# source_eagle.net
KiCad netlist of a schematic drawn in EAGLE
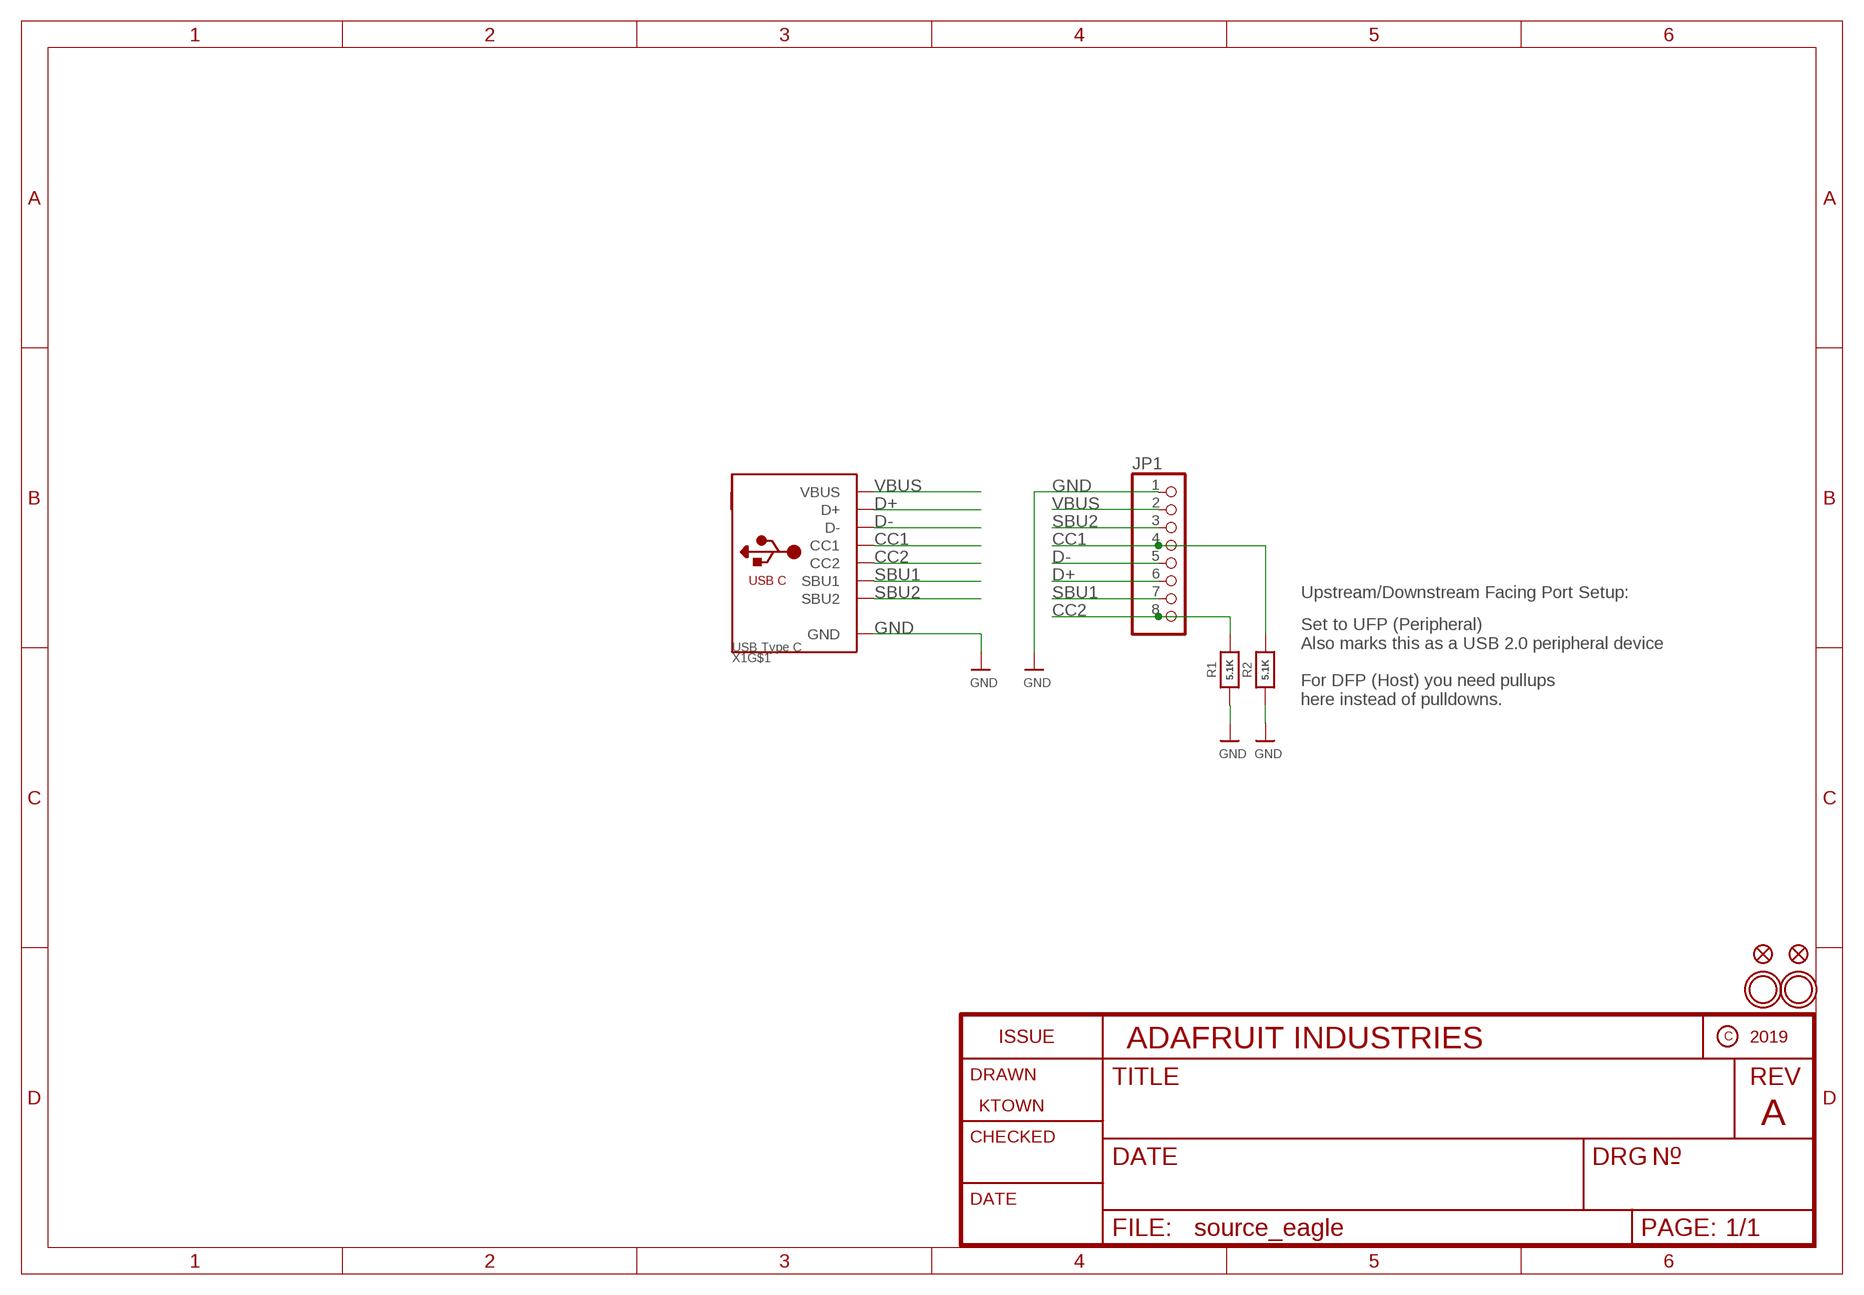
[diagram p0: schematic, sheet 1]

(export (version "E")
  (design (tool "Eeschema 10.0.6"))
  (components
    (comp (ref "FID1")
      (value "FIDUCIAL_0.5MM")
      (footprint "eagle-import:FIDUCIAL_0.5MM")
      (libsource (lib "eagle-import") (part "FIDUCIAL_0.5MM"))
    )
    (comp (ref "FID2")
      (value "FIDUCIAL_0.5MM")
      (footprint "eagle-import:FIDUCIAL_0.5MM")
      (libsource (lib "eagle-import") (part "FIDUCIAL_0.5MM"))
    )
    (comp (ref "JP1")
      (value "HEADER-1X876MIL")
      (footprint "eagle-import:1X08_ROUND_76")
      (libsource (lib "eagle-import") (part "HEADER-1X876MIL"))
    )
    (comp (ref "R1")
      (value "5.1K")
      (footprint "eagle-import:0603-NO")
      (libsource (lib "eagle-import") (part "RESISTOR_0603_NOOUT"))
    )
    (comp (ref "R2")
      (value "5.1K")
      (footprint "eagle-import:0603-NO")
      (libsource (lib "eagle-import") (part "RESISTOR_0603_NOOUT"))
    )
    (comp (ref "U$1")
      (value "MOUNTINGHOLE2.5")
      (footprint "eagle-import:MOUNTINGHOLE_2.5_PLATED")
      (libsource (lib "eagle-import") (part "MOUNTINGHOLE2.5"))
    )
    (comp (ref "U$2")
      (value "MOUNTINGHOLE2.5")
      (footprint "eagle-import:MOUNTINGHOLE_2.5_PLATED")
      (libsource (lib "eagle-import") (part "MOUNTINGHOLE2.5"))
    )
    (comp (ref "X1")
      (value "USB Type C")
      (footprint "eagle-import:USB_C_SINK")
      (libsource (lib "eagle-import") (part "USB_C_SINK"))
    )
  )
  (nets
    (net (code "1") (name "/CC1") (class "Default")
      (node (ref "JP1") (pin "4") (pinfunction "4_4") (pintype "passive"))
      (node (ref "R2") (pin "2") (pinfunction "2_2") (pintype "passive"))
      (node (ref "X1") (pin "A5") (pinfunction "CC1_A5") (pintype "bidirectional"))
    )
    (net (code "2") (name "/CC2") (class "Default")
      (node (ref "JP1") (pin "8") (pinfunction "8_8") (pintype "passive"))
      (node (ref "R1") (pin "2") (pinfunction "2_2") (pintype "passive"))
      (node (ref "X1") (pin "B5") (pinfunction "CC2_B5") (pintype "bidirectional"))
    )
    (net (code "3") (name "/D+") (class "Default")
      (node (ref "JP1") (pin "6") (pinfunction "6_6") (pintype "passive"))
      (node (ref "X1") (pin "A6") (pinfunction "D+_A6") (pintype "bidirectional"))
      (node (ref "X1") (pin "B6") (pinfunction "D+_B6") (pintype "bidirectional"))
    )
    (net (code "4") (name "/D-") (class "Default")
      (node (ref "JP1") (pin "5") (pinfunction "5_5") (pintype "passive"))
      (node (ref "X1") (pin "A7") (pinfunction "D-_A7") (pintype "bidirectional"))
      (node (ref "X1") (pin "B7") (pinfunction "D-_B7") (pintype "bidirectional"))
    )
    (net (code "5") (name "/SBU1") (class "Default")
      (node (ref "JP1") (pin "7") (pinfunction "7_7") (pintype "passive"))
      (node (ref "X1") (pin "A8") (pinfunction "SBU1_A8") (pintype "bidirectional"))
    )
    (net (code "6") (name "/SBU2") (class "Default")
      (node (ref "JP1") (pin "3") (pinfunction "3_3") (pintype "passive"))
      (node (ref "X1") (pin "B8") (pinfunction "SBU2_B8") (pintype "bidirectional"))
    )
    (net (code "7") (name "/VBUS") (class "Default")
      (node (ref "JP1") (pin "2") (pinfunction "2_2") (pintype "passive"))
      (node (ref "X1") (pin "A4B9") (pinfunction "VBUS_A4B9") (pintype "power_in"))
      (node (ref "X1") (pin "B4A9") (pinfunction "VBUS_B4A9") (pintype "power_in"))
    )
    (net (code "8") (name "GND") (class "Default")
      (node (ref "JP1") (pin "1") (pinfunction "1_1") (pintype "passive"))
      (node (ref "R1") (pin "1") (pinfunction "1_1") (pintype "passive"))
      (node (ref "R2") (pin "1") (pinfunction "1_1") (pintype "passive"))
      (node (ref "X1") (pin "A1B12") (pinfunction "GND_A1B12") (pintype "power_in"))
      (node (ref "X1") (pin "B1A12") (pinfunction "GND_B1A12") (pintype "power_in"))
    )
  )
)
